# WS2812RGB.net
KiCad netlist of a schematic drawn in Altium Designer
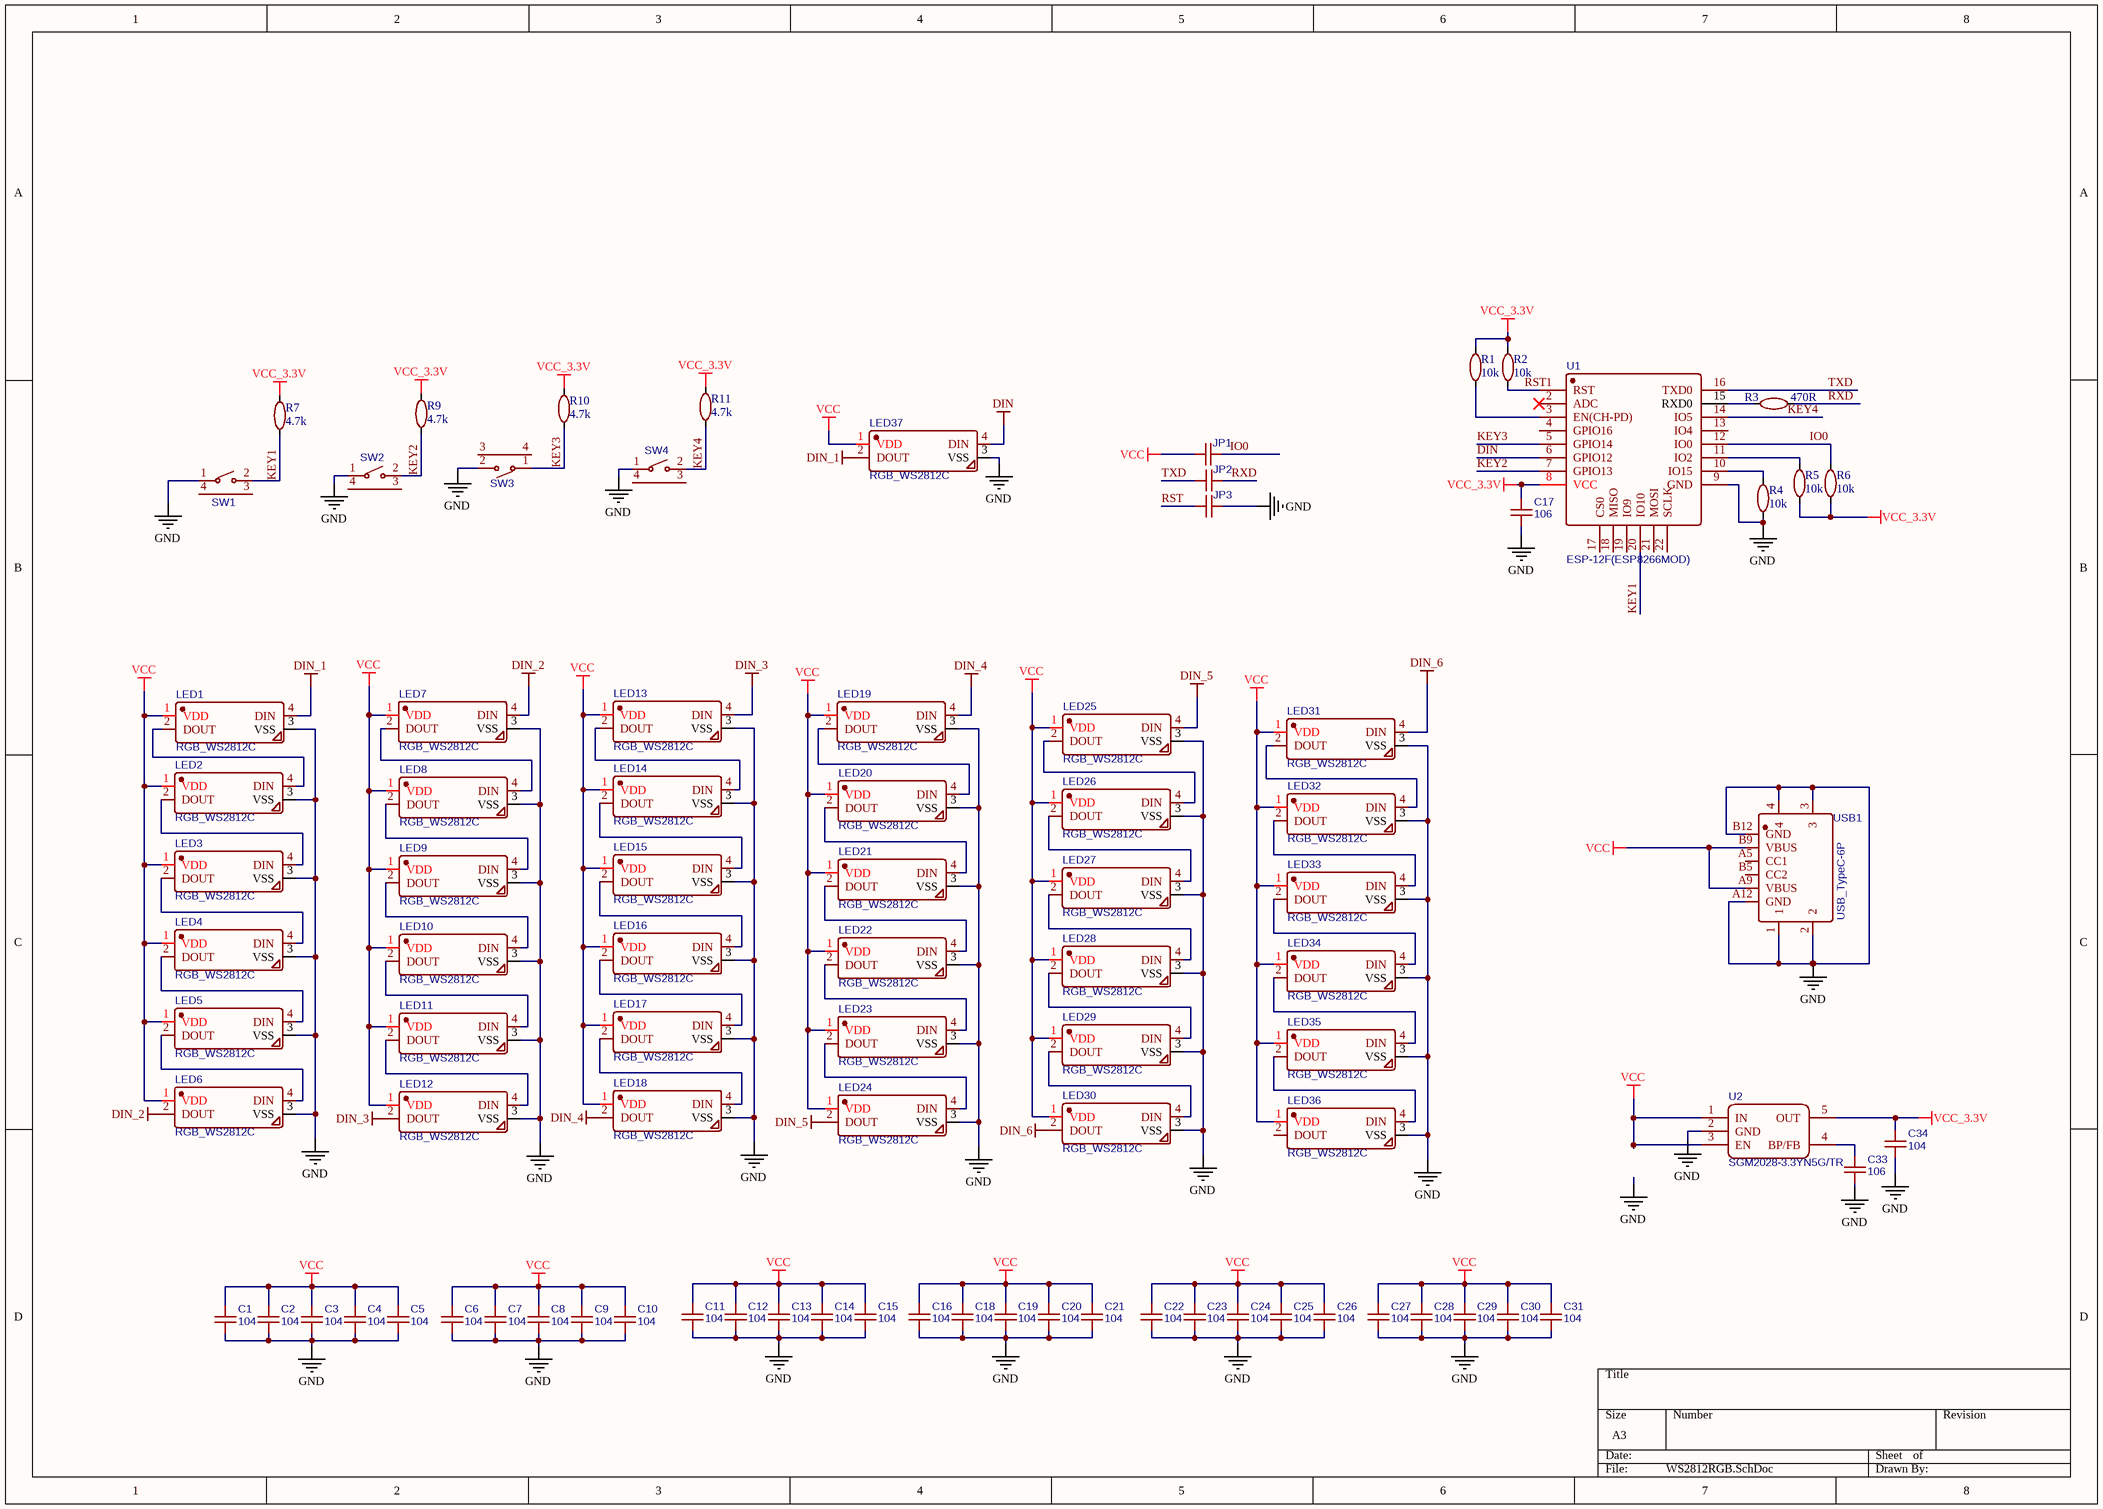
[diagram p0: WS2812RGB.SchDoc]

(export (version "E")
  (design (tool "Eeschema 10.0.6"))
  (components
    (comp (ref "C1")
      (value "104")
      (footprint "CAP_0603")
      (fields
        (field (name "BOM_SUPPLIER PART") "C307348")
        (field (name "BOM_MANUFACTURER PART") "CL10B104KB8WPNC")
        (field (name "CONTRIBUTOR") "LCSC")
      )
      (libsource (lib "LTC_Library1") (part "CAP_0603"))
    )
    (comp (ref "C2")
      (value "104")
      (footprint "CAP_0603")
      (fields
        (field (name "BOM_SUPPLIER PART") "C307348")
        (field (name "BOM_MANUFACTURER PART") "CL10B104KB8WPNC")
        (field (name "CONTRIBUTOR") "LCSC")
      )
      (libsource (lib "LTC_Library1") (part "CAP_0603"))
    )
    (comp (ref "C3")
      (value "104")
      (footprint "CAP_0603")
      (fields
        (field (name "BOM_SUPPLIER PART") "C307348")
        (field (name "BOM_MANUFACTURER PART") "CL10B104KB8WPNC")
        (field (name "CONTRIBUTOR") "LCSC")
      )
      (libsource (lib "LTC_Library1") (part "CAP_0603"))
    )
    (comp (ref "C4")
      (value "104")
      (footprint "CAP_0603")
      (fields
        (field (name "BOM_SUPPLIER PART") "C307348")
        (field (name "BOM_MANUFACTURER PART") "CL10B104KB8WPNC")
        (field (name "CONTRIBUTOR") "LCSC")
      )
      (libsource (lib "LTC_Library1") (part "CAP_0603"))
    )
    (comp (ref "C5")
      (value "104")
      (footprint "CAP_0603")
      (fields
        (field (name "BOM_SUPPLIER PART") "C307348")
        (field (name "BOM_MANUFACTURER PART") "CL10B104KB8WPNC")
        (field (name "CONTRIBUTOR") "LCSC")
      )
      (libsource (lib "LTC_Library1") (part "CAP_0603"))
    )
    (comp (ref "C6")
      (value "104")
      (footprint "CAP_0603")
      (fields
        (field (name "BOM_SUPPLIER PART") "C307348")
        (field (name "BOM_MANUFACTURER PART") "CL10B104KB8WPNC")
        (field (name "CONTRIBUTOR") "LCSC")
      )
      (libsource (lib "LTC_Library1") (part "CAP_0603"))
    )
    (comp (ref "C7")
      (value "104")
      (footprint "CAP_0603")
      (fields
        (field (name "BOM_SUPPLIER PART") "C307348")
        (field (name "BOM_MANUFACTURER PART") "CL10B104KB8WPNC")
        (field (name "CONTRIBUTOR") "LCSC")
      )
      (libsource (lib "LTC_Library1") (part "CAP_0603"))
    )
    (comp (ref "C8")
      (value "104")
      (footprint "CAP_0603")
      (fields
        (field (name "BOM_SUPPLIER PART") "C307348")
        (field (name "BOM_MANUFACTURER PART") "CL10B104KB8WPNC")
        (field (name "CONTRIBUTOR") "LCSC")
      )
      (libsource (lib "LTC_Library1") (part "CAP_0603"))
    )
    (comp (ref "C9")
      (value "104")
      (footprint "CAP_0603")
      (fields
        (field (name "BOM_SUPPLIER PART") "C307348")
        (field (name "BOM_MANUFACTURER PART") "CL10B104KB8WPNC")
        (field (name "CONTRIBUTOR") "LCSC")
      )
      (libsource (lib "LTC_Library1") (part "CAP_0603"))
    )
    (comp (ref "C10")
      (value "104")
      (footprint "CAP_0603")
      (fields
        (field (name "BOM_SUPPLIER PART") "C307348")
        (field (name "BOM_MANUFACTURER PART") "CL10B104KB8WPNC")
        (field (name "CONTRIBUTOR") "LCSC")
      )
      (libsource (lib "LTC_Library1") (part "CAP_0603"))
    )
    (comp (ref "C11")
      (value "104")
      (footprint "CAP_0603")
      (fields
        (field (name "BOM_SUPPLIER PART") "C307348")
        (field (name "BOM_MANUFACTURER PART") "CL10B104KB8WPNC")
        (field (name "CONTRIBUTOR") "LCSC")
      )
      (libsource (lib "LTC_Library1") (part "CAP_0603"))
    )
    (comp (ref "C12")
      (value "104")
      (footprint "CAP_0603")
      (fields
        (field (name "BOM_SUPPLIER PART") "C307348")
        (field (name "BOM_MANUFACTURER PART") "CL10B104KB8WPNC")
        (field (name "CONTRIBUTOR") "LCSC")
      )
      (libsource (lib "LTC_Library1") (part "CAP_0603"))
    )
    (comp (ref "C13")
      (value "104")
      (footprint "CAP_0603")
      (fields
        (field (name "BOM_SUPPLIER PART") "C307348")
        (field (name "BOM_MANUFACTURER PART") "CL10B104KB8WPNC")
        (field (name "CONTRIBUTOR") "LCSC")
      )
      (libsource (lib "LTC_Library1") (part "CAP_0603"))
    )
    (comp (ref "C14")
      (value "104")
      (footprint "CAP_0603")
      (fields
        (field (name "BOM_SUPPLIER PART") "C307348")
        (field (name "BOM_MANUFACTURER PART") "CL10B104KB8WPNC")
        (field (name "CONTRIBUTOR") "LCSC")
      )
      (libsource (lib "LTC_Library1") (part "CAP_0603"))
    )
    (comp (ref "C15")
      (value "104")
      (footprint "CAP_0603")
      (fields
        (field (name "BOM_SUPPLIER PART") "C307348")
        (field (name "BOM_MANUFACTURER PART") "CL10B104KB8WPNC")
        (field (name "CONTRIBUTOR") "LCSC")
      )
      (libsource (lib "LTC_Library1") (part "CAP_0603"))
    )
    (comp (ref "C16")
      (value "104")
      (footprint "CAP_0603")
      (fields
        (field (name "BOM_SUPPLIER PART") "C307348")
        (field (name "BOM_MANUFACTURER PART") "CL10B104KB8WPNC")
        (field (name "CONTRIBUTOR") "LCSC")
      )
      (libsource (lib "LTC_Library1") (part "CAP_0603"))
    )
    (comp (ref "C17")
      (value "106")
      (footprint "CAP_0603")
      (fields
        (field (name "BOM_SUPPLIER PART") "C307348")
        (field (name "BOM_MANUFACTURER PART") "CL10B104KB8WPNC")
        (field (name "CONTRIBUTOR") "LCSC")
      )
      (libsource (lib "LTC_Library1") (part "CAP_0603"))
    )
    (comp (ref "C18")
      (value "104")
      (footprint "CAP_0603")
      (fields
        (field (name "BOM_SUPPLIER PART") "C307348")
        (field (name "BOM_MANUFACTURER PART") "CL10B104KB8WPNC")
        (field (name "CONTRIBUTOR") "LCSC")
      )
      (libsource (lib "LTC_Library1") (part "CAP_0603"))
    )
    (comp (ref "C19")
      (value "104")
      (footprint "CAP_0603")
      (fields
        (field (name "BOM_SUPPLIER PART") "C307348")
        (field (name "BOM_MANUFACTURER PART") "CL10B104KB8WPNC")
        (field (name "CONTRIBUTOR") "LCSC")
      )
      (libsource (lib "LTC_Library1") (part "CAP_0603"))
    )
    (comp (ref "C20")
      (value "104")
      (footprint "CAP_0603")
      (fields
        (field (name "BOM_SUPPLIER PART") "C307348")
        (field (name "BOM_MANUFACTURER PART") "CL10B104KB8WPNC")
        (field (name "CONTRIBUTOR") "LCSC")
      )
      (libsource (lib "LTC_Library1") (part "CAP_0603"))
    )
    (comp (ref "C21")
      (value "104")
      (footprint "CAP_0603")
      (fields
        (field (name "BOM_SUPPLIER PART") "C307348")
        (field (name "BOM_MANUFACTURER PART") "CL10B104KB8WPNC")
        (field (name "CONTRIBUTOR") "LCSC")
      )
      (libsource (lib "LTC_Library1") (part "CAP_0603"))
    )
    (comp (ref "C22")
      (value "104")
      (footprint "CAP_0603")
      (fields
        (field (name "BOM_SUPPLIER PART") "C307348")
        (field (name "BOM_MANUFACTURER PART") "CL10B104KB8WPNC")
        (field (name "CONTRIBUTOR") "LCSC")
      )
      (libsource (lib "LTC_Library1") (part "CAP_0603"))
    )
    (comp (ref "C23")
      (value "104")
      (footprint "CAP_0603")
      (fields
        (field (name "BOM_SUPPLIER PART") "C307348")
        (field (name "BOM_MANUFACTURER PART") "CL10B104KB8WPNC")
        (field (name "CONTRIBUTOR") "LCSC")
      )
      (libsource (lib "LTC_Library1") (part "CAP_0603"))
    )
    (comp (ref "C24")
      (value "104")
      (footprint "CAP_0603")
      (fields
        (field (name "BOM_SUPPLIER PART") "C307348")
        (field (name "BOM_MANUFACTURER PART") "CL10B104KB8WPNC")
        (field (name "CONTRIBUTOR") "LCSC")
      )
      (libsource (lib "LTC_Library1") (part "CAP_0603"))
    )
    (comp (ref "C25")
      (value "104")
      (footprint "CAP_0603")
      (fields
        (field (name "BOM_SUPPLIER PART") "C307348")
        (field (name "BOM_MANUFACTURER PART") "CL10B104KB8WPNC")
        (field (name "CONTRIBUTOR") "LCSC")
      )
      (libsource (lib "LTC_Library1") (part "CAP_0603"))
    )
    (comp (ref "C26")
      (value "104")
      (footprint "CAP_0603")
      (fields
        (field (name "BOM_SUPPLIER PART") "C307348")
        (field (name "BOM_MANUFACTURER PART") "CL10B104KB8WPNC")
        (field (name "CONTRIBUTOR") "LCSC")
      )
      (libsource (lib "LTC_Library1") (part "CAP_0603"))
    )
    (comp (ref "C27")
      (value "104")
      (footprint "CAP_0603")
      (fields
        (field (name "BOM_SUPPLIER PART") "C307348")
        (field (name "BOM_MANUFACTURER PART") "CL10B104KB8WPNC")
        (field (name "CONTRIBUTOR") "LCSC")
      )
      (libsource (lib "LTC_Library1") (part "CAP_0603"))
    )
    (comp (ref "C28")
      (value "104")
      (footprint "CAP_0603")
      (fields
        (field (name "BOM_SUPPLIER PART") "C307348")
        (field (name "BOM_MANUFACTURER PART") "CL10B104KB8WPNC")
        (field (name "CONTRIBUTOR") "LCSC")
      )
      (libsource (lib "LTC_Library1") (part "CAP_0603"))
    )
    (comp (ref "C29")
      (value "104")
      (footprint "CAP_0603")
      (fields
        (field (name "BOM_SUPPLIER PART") "C307348")
        (field (name "BOM_MANUFACTURER PART") "CL10B104KB8WPNC")
        (field (name "CONTRIBUTOR") "LCSC")
      )
      (libsource (lib "LTC_Library1") (part "CAP_0603"))
    )
    (comp (ref "C30")
      (value "104")
      (footprint "CAP_0603")
      (fields
        (field (name "BOM_SUPPLIER PART") "C307348")
        (field (name "BOM_MANUFACTURER PART") "CL10B104KB8WPNC")
        (field (name "CONTRIBUTOR") "LCSC")
      )
      (libsource (lib "LTC_Library1") (part "CAP_0603"))
    )
    (comp (ref "C31")
      (value "104")
      (footprint "CAP_0603")
      (fields
        (field (name "BOM_SUPPLIER PART") "C307348")
        (field (name "BOM_MANUFACTURER PART") "CL10B104KB8WPNC")
        (field (name "CONTRIBUTOR") "LCSC")
      )
      (libsource (lib "LTC_Library1") (part "CAP_0603"))
    )
    (comp (ref "C33")
      (value "106")
      (footprint "CAP_0603")
      (fields
        (field (name "BOM_SUPPLIER PART") "C307348")
        (field (name "BOM_MANUFACTURER PART") "CL10B104KB8WPNC")
        (field (name "CONTRIBUTOR") "LCSC")
      )
      (libsource (lib "LTC_Library1") (part "CAP_0603"))
    )
    (comp (ref "C34")
      (value "104")
      (footprint "CAP_0603")
      (fields
        (field (name "BOM_SUPPLIER PART") "C307348")
        (field (name "BOM_MANUFACTURER PART") "CL10B104KB8WPNC")
        (field (name "CONTRIBUTOR") "LCSC")
      )
      (libsource (lib "LTC_Library1") (part "CAP_0603"))
    )
    (comp (ref "JP1")
      (value "104")
      (footprint "CAP_0805")
      (fields
        (field (name "BOM_SUPPLIER PART") "C307348")
        (field (name "BOM_MANUFACTURER PART") "CL10B104KB8WPNC")
        (field (name "CONTRIBUTOR") "LCSC")
      )
      (libsource (lib "LTC_Library1") (part "CAP_0805"))
    )
    (comp (ref "JP2")
      (value "104")
      (footprint "CAP_0805")
      (fields
        (field (name "BOM_SUPPLIER PART") "C307348")
        (field (name "BOM_MANUFACTURER PART") "CL10B104KB8WPNC")
        (field (name "CONTRIBUTOR") "LCSC")
      )
      (libsource (lib "LTC_Library1") (part "CAP_0805"))
    )
    (comp (ref "JP3")
      (value "104")
      (footprint "CAP_0805")
      (fields
        (field (name "BOM_SUPPLIER PART") "C307348")
        (field (name "BOM_MANUFACTURER PART") "CL10B104KB8WPNC")
        (field (name "CONTRIBUTOR") "LCSC")
      )
      (libsource (lib "LTC_Library1") (part "CAP_0805"))
    )
    (comp (ref "LED1")
      (value "RGB_WS2812C")
      (footprint "LED_5050-SMD_4P-WS2812")
      (fields
        (field (name "BOM_MANUFACTURER PART") "WS2812C")
        (field (name "BOM_SUPPLIER PART") "C114587")
        (field (name "CONTRIBUTOR") "LCSC")
      )
      (libsource (lib "LTC_Library1") (part "RGB_WS2812C"))
    )
    (comp (ref "LED2")
      (value "RGB_WS2812C")
      (footprint "LED_5050-SMD_4P-WS2812")
      (fields
        (field (name "BOM_MANUFACTURER PART") "WS2812C")
        (field (name "BOM_SUPPLIER PART") "C114587")
        (field (name "CONTRIBUTOR") "LCSC")
      )
      (libsource (lib "LTC_Library1") (part "RGB_WS2812C"))
    )
    (comp (ref "LED3")
      (value "RGB_WS2812C")
      (footprint "LED_5050-SMD_4P-WS2812")
      (fields
        (field (name "BOM_MANUFACTURER PART") "WS2812C")
        (field (name "BOM_SUPPLIER PART") "C114587")
        (field (name "CONTRIBUTOR") "LCSC")
      )
      (libsource (lib "LTC_Library1") (part "RGB_WS2812C"))
    )
    (comp (ref "LED4")
      (value "RGB_WS2812C")
      (footprint "LED_5050-SMD_4P-WS2812")
      (fields
        (field (name "BOM_MANUFACTURER PART") "WS2812C")
        (field (name "BOM_SUPPLIER PART") "C114587")
        (field (name "CONTRIBUTOR") "LCSC")
      )
      (libsource (lib "LTC_Library1") (part "RGB_WS2812C"))
    )
    (comp (ref "LED5")
      (value "RGB_WS2812C")
      (footprint "LED_5050-SMD_4P-WS2812")
      (fields
        (field (name "BOM_MANUFACTURER PART") "WS2812C")
        (field (name "BOM_SUPPLIER PART") "C114587")
        (field (name "CONTRIBUTOR") "LCSC")
      )
      (libsource (lib "LTC_Library1") (part "RGB_WS2812C"))
    )
    (comp (ref "LED6")
      (value "RGB_WS2812C")
      (footprint "LED_5050-SMD_4P-WS2812")
      (fields
        (field (name "BOM_MANUFACTURER PART") "WS2812C")
        (field (name "BOM_SUPPLIER PART") "C114587")
        (field (name "CONTRIBUTOR") "LCSC")
      )
      (libsource (lib "LTC_Library1") (part "RGB_WS2812C"))
    )
    (comp (ref "LED7")
      (value "RGB_WS2812C")
      (footprint "LED_5050-SMD_4P-WS2812")
      (fields
        (field (name "BOM_MANUFACTURER PART") "WS2812C")
        (field (name "BOM_SUPPLIER PART") "C114587")
        (field (name "CONTRIBUTOR") "LCSC")
      )
      (libsource (lib "LTC_Library1") (part "RGB_WS2812C"))
    )
    (comp (ref "LED8")
      (value "RGB_WS2812C")
      (footprint "LED_5050-SMD_4P-WS2812")
      (fields
        (field (name "BOM_MANUFACTURER PART") "WS2812C")
        (field (name "BOM_SUPPLIER PART") "C114587")
        (field (name "CONTRIBUTOR") "LCSC")
      )
      (libsource (lib "LTC_Library1") (part "RGB_WS2812C"))
    )
    (comp (ref "LED9")
      (value "RGB_WS2812C")
      (footprint "LED_5050-SMD_4P-WS2812")
      (fields
        (field (name "BOM_MANUFACTURER PART") "WS2812C")
        (field (name "BOM_SUPPLIER PART") "C114587")
        (field (name "CONTRIBUTOR") "LCSC")
      )
      (libsource (lib "LTC_Library1") (part "RGB_WS2812C"))
    )
    (comp (ref "LED10")
      (value "RGB_WS2812C")
      (footprint "LED_5050-SMD_4P-WS2812")
      (fields
        (field (name "BOM_MANUFACTURER PART") "WS2812C")
        (field (name "BOM_SUPPLIER PART") "C114587")
        (field (name "CONTRIBUTOR") "LCSC")
      )
      (libsource (lib "LTC_Library1") (part "RGB_WS2812C"))
    )
    (comp (ref "LED11")
      (value "RGB_WS2812C")
      (footprint "LED_5050-SMD_4P-WS2812")
      (fields
        (field (name "BOM_MANUFACTURER PART") "WS2812C")
        (field (name "BOM_SUPPLIER PART") "C114587")
        (field (name "CONTRIBUTOR") "LCSC")
      )
      (libsource (lib "LTC_Library1") (part "RGB_WS2812C"))
    )
    (comp (ref "LED12")
      (value "RGB_WS2812C")
      (footprint "LED_5050-SMD_4P-WS2812")
      (fields
        (field (name "BOM_MANUFACTURER PART") "WS2812C")
        (field (name "BOM_SUPPLIER PART") "C114587")
        (field (name "CONTRIBUTOR") "LCSC")
      )
      (libsource (lib "LTC_Library1") (part "RGB_WS2812C"))
    )
    (comp (ref "LED13")
      (value "RGB_WS2812C")
      (footprint "LED_5050-SMD_4P-WS2812")
      (fields
        (field (name "BOM_MANUFACTURER PART") "WS2812C")
        (field (name "BOM_SUPPLIER PART") "C114587")
        (field (name "CONTRIBUTOR") "LCSC")
      )
      (libsource (lib "LTC_Library1") (part "RGB_WS2812C"))
    )
    (comp (ref "LED14")
      (value "RGB_WS2812C")
      (footprint "LED_5050-SMD_4P-WS2812")
      (fields
        (field (name "BOM_MANUFACTURER PART") "WS2812C")
        (field (name "BOM_SUPPLIER PART") "C114587")
        (field (name "CONTRIBUTOR") "LCSC")
      )
      (libsource (lib "LTC_Library1") (part "RGB_WS2812C"))
    )
    (comp (ref "LED15")
      (value "RGB_WS2812C")
      (footprint "LED_5050-SMD_4P-WS2812")
      (fields
        (field (name "BOM_MANUFACTURER PART") "WS2812C")
        (field (name "BOM_SUPPLIER PART") "C114587")
        (field (name "CONTRIBUTOR") "LCSC")
      )
      (libsource (lib "LTC_Library1") (part "RGB_WS2812C"))
    )
    (comp (ref "LED16")
      (value "RGB_WS2812C")
      (footprint "LED_5050-SMD_4P-WS2812")
      (fields
        (field (name "BOM_MANUFACTURER PART") "WS2812C")
        (field (name "BOM_SUPPLIER PART") "C114587")
        (field (name "CONTRIBUTOR") "LCSC")
      )
      (libsource (lib "LTC_Library1") (part "RGB_WS2812C"))
    )
    (comp (ref "LED17")
      (value "RGB_WS2812C")
      (footprint "LED_5050-SMD_4P-WS2812")
      (fields
        (field (name "BOM_MANUFACTURER PART") "WS2812C")
        (field (name "BOM_SUPPLIER PART") "C114587")
        (field (name "CONTRIBUTOR") "LCSC")
      )
      (libsource (lib "LTC_Library1") (part "RGB_WS2812C"))
    )
    (comp (ref "LED18")
      (value "RGB_WS2812C")
      (footprint "LED_5050-SMD_4P-WS2812")
      (fields
        (field (name "BOM_MANUFACTURER PART") "WS2812C")
        (field (name "BOM_SUPPLIER PART") "C114587")
        (field (name "CONTRIBUTOR") "LCSC")
      )
      (libsource (lib "LTC_Library1") (part "RGB_WS2812C"))
    )
    (comp (ref "LED19")
      (value "RGB_WS2812C")
      (footprint "LED_5050-SMD_4P-WS2812")
      (fields
        (field (name "BOM_MANUFACTURER PART") "WS2812C")
        (field (name "BOM_SUPPLIER PART") "C114587")
        (field (name "CONTRIBUTOR") "LCSC")
      )
      (libsource (lib "LTC_Library1") (part "RGB_WS2812C"))
    )
    (comp (ref "LED20")
      (value "RGB_WS2812C")
      (footprint "LED_5050-SMD_4P-WS2812")
      (fields
        (field (name "BOM_MANUFACTURER PART") "WS2812C")
        (field (name "BOM_SUPPLIER PART") "C114587")
        (field (name "CONTRIBUTOR") "LCSC")
      )
      (libsource (lib "LTC_Library1") (part "RGB_WS2812C"))
    )
    (comp (ref "LED21")
      (value "RGB_WS2812C")
      (footprint "LED_5050-SMD_4P-WS2812")
      (fields
        (field (name "BOM_MANUFACTURER PART") "WS2812C")
        (field (name "BOM_SUPPLIER PART") "C114587")
        (field (name "CONTRIBUTOR") "LCSC")
      )
      (libsource (lib "LTC_Library1") (part "RGB_WS2812C"))
    )
    (comp (ref "LED22")
      (value "RGB_WS2812C")
      (footprint "LED_5050-SMD_4P-WS2812")
      (fields
        (field (name "BOM_MANUFACTURER PART") "WS2812C")
        (field (name "BOM_SUPPLIER PART") "C114587")
        (field (name "CONTRIBUTOR") "LCSC")
      )
      (libsource (lib "LTC_Library1") (part "RGB_WS2812C"))
    )
    (comp (ref "LED23")
      (value "RGB_WS2812C")
      (footprint "LED_5050-SMD_4P-WS2812")
      (fields
        (field (name "BOM_MANUFACTURER PART") "WS2812C")
        (field (name "BOM_SUPPLIER PART") "C114587")
        (field (name "CONTRIBUTOR") "LCSC")
      )
      (libsource (lib "LTC_Library1") (part "RGB_WS2812C"))
    )
    (comp (ref "LED24")
      (value "RGB_WS2812C")
      (footprint "LED_5050-SMD_4P-WS2812")
      (fields
        (field (name "BOM_MANUFACTURER PART") "WS2812C")
        (field (name "BOM_SUPPLIER PART") "C114587")
        (field (name "CONTRIBUTOR") "LCSC")
      )
      (libsource (lib "LTC_Library1") (part "RGB_WS2812C"))
    )
    (comp (ref "LED25")
      (value "RGB_WS2812C")
      (footprint "LED_5050-SMD_4P-WS2812")
      (fields
        (field (name "BOM_MANUFACTURER PART") "WS2812C")
        (field (name "BOM_SUPPLIER PART") "C114587")
        (field (name "CONTRIBUTOR") "LCSC")
      )
      (libsource (lib "LTC_Library1") (part "RGB_WS2812C"))
    )
    (comp (ref "LED26")
      (value "RGB_WS2812C")
      (footprint "LED_5050-SMD_4P-WS2812")
      (fields
        (field (name "BOM_MANUFACTURER PART") "WS2812C")
        (field (name "BOM_SUPPLIER PART") "C114587")
        (field (name "CONTRIBUTOR") "LCSC")
      )
      (libsource (lib "LTC_Library1") (part "RGB_WS2812C"))
    )
    (comp (ref "LED27")
      (value "RGB_WS2812C")
      (footprint "LED_5050-SMD_4P-WS2812")
      (fields
        (field (name "BOM_MANUFACTURER PART") "WS2812C")
        (field (name "BOM_SUPPLIER PART") "C114587")
        (field (name "CONTRIBUTOR") "LCSC")
      )
      (libsource (lib "LTC_Library1") (part "RGB_WS2812C"))
    )
    (comp (ref "LED28")
      (value "RGB_WS2812C")
      (footprint "LED_5050-SMD_4P-WS2812")
      (fields
        (field (name "BOM_MANUFACTURER PART") "WS2812C")
        (field (name "BOM_SUPPLIER PART") "C114587")
        (field (name "CONTRIBUTOR") "LCSC")
      )
      (libsource (lib "LTC_Library1") (part "RGB_WS2812C"))
    )
    (comp (ref "LED29")
      (value "RGB_WS2812C")
      (footprint "LED_5050-SMD_4P-WS2812")
      (fields
        (field (name "BOM_MANUFACTURER PART") "WS2812C")
        (field (name "BOM_SUPPLIER PART") "C114587")
        (field (name "CONTRIBUTOR") "LCSC")
      )
      (libsource (lib "LTC_Library1") (part "RGB_WS2812C"))
    )
    (comp (ref "LED30")
      (value "RGB_WS2812C")
      (footprint "LED_5050-SMD_4P-WS2812")
      (fields
        (field (name "BOM_MANUFACTURER PART") "WS2812C")
        (field (name "BOM_SUPPLIER PART") "C114587")
        (field (name "CONTRIBUTOR") "LCSC")
      )
      (libsource (lib "LTC_Library1") (part "RGB_WS2812C"))
    )
    (comp (ref "LED31")
      (value "RGB_WS2812C")
      (footprint "LED_5050-SMD_4P-WS2812")
      (fields
        (field (name "BOM_MANUFACTURER PART") "WS2812C")
        (field (name "BOM_SUPPLIER PART") "C114587")
        (field (name "CONTRIBUTOR") "LCSC")
      )
      (libsource (lib "LTC_Library1") (part "RGB_WS2812C"))
    )
    (comp (ref "LED32")
      (value "RGB_WS2812C")
      (footprint "LED_5050-SMD_4P-WS2812")
      (fields
        (field (name "BOM_MANUFACTURER PART") "WS2812C")
        (field (name "BOM_SUPPLIER PART") "C114587")
        (field (name "CONTRIBUTOR") "LCSC")
      )
      (libsource (lib "LTC_Library1") (part "RGB_WS2812C"))
    )
    (comp (ref "LED33")
      (value "RGB_WS2812C")
      (footprint "LED_5050-SMD_4P-WS2812")
      (fields
        (field (name "BOM_MANUFACTURER PART") "WS2812C")
        (field (name "BOM_SUPPLIER PART") "C114587")
        (field (name "CONTRIBUTOR") "LCSC")
      )
      (libsource (lib "LTC_Library1") (part "RGB_WS2812C"))
    )
    (comp (ref "LED34")
      (value "RGB_WS2812C")
      (footprint "LED_5050-SMD_4P-WS2812")
      (fields
        (field (name "BOM_MANUFACTURER PART") "WS2812C")
        (field (name "BOM_SUPPLIER PART") "C114587")
        (field (name "CONTRIBUTOR") "LCSC")
      )
      (libsource (lib "LTC_Library1") (part "RGB_WS2812C"))
    )
    (comp (ref "LED35")
      (value "RGB_WS2812C")
      (footprint "LED_5050-SMD_4P-WS2812")
      (fields
        (field (name "BOM_MANUFACTURER PART") "WS2812C")
        (field (name "BOM_SUPPLIER PART") "C114587")
        (field (name "CONTRIBUTOR") "LCSC")
      )
      (libsource (lib "LTC_Library1") (part "RGB_WS2812C"))
    )
    (comp (ref "LED36")
      (value "RGB_WS2812C")
      (footprint "LED_5050-SMD_4P-WS2812")
      (fields
        (field (name "BOM_MANUFACTURER PART") "WS2812C")
        (field (name "BOM_SUPPLIER PART") "C114587")
        (field (name "CONTRIBUTOR") "LCSC")
      )
      (libsource (lib "LTC_Library1") (part "RGB_WS2812C"))
    )
    (comp (ref "LED37")
      (value "RGB_WS2812C")
      (footprint "LED_5050-SMD_4P-WS2812")
      (fields
        (field (name "BOM_MANUFACTURER PART") "WS2812C")
        (field (name "BOM_SUPPLIER PART") "C114587")
        (field (name "CONTRIBUTOR") "LCSC")
      )
      (libsource (lib "LTC_Library1") (part "RGB_WS2812C"))
    )
    (comp (ref "R1") (value "10k") (footprint "RES_0402") (libsource (lib "LTC_Library1") (part "RES_0402")))
    (comp (ref "R2") (value "10k") (footprint "RES_0402") (libsource (lib "LTC_Library1") (part "RES_0402")))
    (comp (ref "R3") (value "470R") (footprint "RES_0402") (libsource (lib "LTC_Library1") (part "RES_0402")))
    (comp (ref "R4") (value "10k") (footprint "RES_0402") (libsource (lib "LTC_Library1") (part "RES_0402")))
    (comp (ref "R5") (value "10k") (footprint "RES_0402") (libsource (lib "LTC_Library1") (part "RES_0402")))
    (comp (ref "R6") (value "10k") (footprint "RES_0402") (libsource (lib "LTC_Library1") (part "RES_0402")))
    (comp (ref "R7") (value "4.7k") (footprint "RES_0402") (libsource (lib "LTC_Library1") (part "RES_0402")))
    (comp (ref "R9") (value "4.7k") (footprint "RES_0402") (libsource (lib "LTC_Library1") (part "RES_0402")))
    (comp (ref "R10")
      (value "4.7k")
      (footprint "RES_0402")
      (libsource (lib "LTC_Library1") (part "RES_0402"))
    )
    (comp (ref "R11")
      (value "4.7k")
      (footprint "RES_0402")
      (libsource (lib "LTC_Library1") (part "RES_0402"))
    )
    (comp (ref "SW1")
      (value "TS-1086E-16")
      (footprint "SW-SMD_TS-1086E-16")
      (fields (field (name "BOM_SUPPLIER PART") "C455276") (field (name "CONTRIBUTOR") "LCSC"))
      (libsource (lib "LTC_Library1") (part "TS-1086E-16"))
    )
    (comp (ref "SW2")
      (value "TS-1086E-16")
      (footprint "SW-SMD_TS-1086E-16")
      (fields (field (name "BOM_SUPPLIER PART") "C455276") (field (name "CONTRIBUTOR") "LCSC"))
      (libsource (lib "LTC_Library1") (part "TS-1086E-16"))
    )
    (comp (ref "SW3")
      (value "TS-1086E-16")
      (footprint "SW-SMD_TS-1086E-16")
      (fields (field (name "BOM_SUPPLIER PART") "C455276") (field (name "CONTRIBUTOR") "LCSC"))
      (libsource (lib "LTC_Library1") (part "TS-1086E-16"))
    )
    (comp (ref "SW4")
      (value "TS-1086E-16")
      (footprint "SW-SMD_TS-1086E-16")
      (fields (field (name "BOM_SUPPLIER PART") "C455276") (field (name "CONTRIBUTOR") "LCSC"))
      (libsource (lib "LTC_Library1") (part "TS-1086E-16"))
    )
    (comp (ref "U1")
      (value "ESP-12F(ESP8266MOD)")
      (footprint "WIFIM-SMD_ESP-12F-ESP8266MOD")
      (fields (field (name "BOM_SUPPLIER PART") "C82891"))
      (libsource (lib "LTC_Library1") (part "ESP-12F(ESP8266MOD)"))
    )
    (comp (ref "U2")
      (value "SGM2028-3.3YN5G/TR")
      (footprint "SOT23_5")
      (fields (field (name "BOM_SUPPLIER PART") "C81088"))
      (libsource (lib "LTC_Library1") (part "SGM2028-3.3YN5G/TR"))
    )
    (comp (ref "USB1")
      (value "USB_TypeC-6P")
      (footprint "USB-TYPE-C-SMD")
      (fields
        (field (name "BOM_SUPPLIER PART") "C399925")
        (field (name "BOM_MANUFACTURER PART") "918-418K2023S40006")
        (field (name "CONTRIBUTOR") "LCSC")
      )
      (libsource (lib "LTC_Library1") (part "USB_TypeC-6P"))
    )
  )
  (nets
    (net (code "1") (name "/IO0") (class "Default")
      (node (ref "JP1") (pin "2") (pinfunction "2_2") (pintype "passive"))
      (node (ref "R6") (pin "1") (pinfunction "1_1") (pintype "passive"))
      (node (ref "U1") (pin "12") (pinfunction "IO0_12") (pintype "passive"))
    )
    (net (code "2") (name "/KEY1") (class "Default")
      (node (ref "R7") (pin "2") (pinfunction "2_2") (pintype "passive"))
      (node (ref "SW1") (pin "2") (pinfunction "2_2") (pintype "passive"))
      (node (ref "U1") (pin "20") (pinfunction "IO10_20") (pintype "passive"))
    )
    (net (code "3") (name "/KEY2") (class "Default")
      (node (ref "R9") (pin "2") (pinfunction "2_2") (pintype "passive"))
      (node (ref "SW2") (pin "2") (pinfunction "2_2") (pintype "passive"))
      (node (ref "U1") (pin "7") (pinfunction "GPIO13_7") (pintype "passive"))
    )
    (net (code "4") (name "/KEY3") (class "Default")
      (node (ref "R10") (pin "2") (pinfunction "2_2") (pintype "passive"))
      (node (ref "SW3") (pin "1") (pinfunction "1_1") (pintype "passive"))
      (node (ref "U1") (pin "5") (pinfunction "GPIO14_5") (pintype "passive"))
    )
    (net (code "5") (name "/KEY4") (class "Default")
      (node (ref "R11") (pin "2") (pinfunction "2_2") (pintype "passive"))
      (node (ref "SW4") (pin "2") (pinfunction "2_2") (pintype "passive"))
      (node (ref "U1") (pin "14") (pinfunction "IO5_14") (pintype "passive"))
    )
    (net (code "6") (name "/RST") (class "Default")
      (node (ref "JP3") (pin "1") (pinfunction "1_1") (pintype "passive"))
      (node (ref "R2") (pin "2") (pinfunction "2_2") (pintype "passive"))
      (node (ref "U1") (pin "1") (pinfunction "RST_1") (pintype "passive"))
    )
    (net (code "7") (name "/RXD") (class "Default")
      (node (ref "JP2") (pin "2") (pinfunction "2_2") (pintype "passive"))
      (node (ref "R3") (pin "2") (pinfunction "2_2") (pintype "passive"))
    )
    (net (code "8") (name "/TXD") (class "Default")
      (node (ref "JP2") (pin "1") (pinfunction "1_1") (pintype "passive"))
      (node (ref "U1") (pin "16") (pinfunction "TXD0_16") (pintype "passive"))
    )
    (net (code "9") (name "DIN") (class "Default")
      (node (ref "LED37") (pin "4") (pinfunction "DIN_4") (pintype "passive"))
      (node (ref "U1") (pin "6") (pinfunction "GPIO12_6") (pintype "passive"))
    )
    (net (code "10") (name "DIN_1") (class "Default")
      (node (ref "LED1") (pin "4") (pinfunction "DIN_4") (pintype "passive"))
      (node (ref "LED37") (pin "2") (pinfunction "DOUT_2") (pintype "passive"))
    )
    (net (code "11") (name "DIN_2") (class "Default")
      (node (ref "LED6") (pin "2") (pinfunction "DOUT_2") (pintype "passive"))
      (node (ref "LED7") (pin "4") (pinfunction "DIN_4") (pintype "passive"))
    )
    (net (code "12") (name "DIN_3") (class "Default")
      (node (ref "LED12") (pin "2") (pinfunction "DOUT_2") (pintype "passive"))
      (node (ref "LED13") (pin "4") (pinfunction "DIN_4") (pintype "passive"))
    )
    (net (code "13") (name "DIN_4") (class "Default")
      (node (ref "LED18") (pin "2") (pinfunction "DOUT_2") (pintype "passive"))
      (node (ref "LED19") (pin "4") (pinfunction "DIN_4") (pintype "passive"))
    )
    (net (code "14") (name "DIN_5") (class "Default")
      (node (ref "LED24") (pin "2") (pinfunction "DOUT_2") (pintype "passive"))
      (node (ref "LED25") (pin "4") (pinfunction "DIN_4") (pintype "passive"))
    )
    (net (code "15") (name "DIN_6") (class "Default")
      (node (ref "LED30") (pin "2") (pinfunction "DOUT_2") (pintype "passive"))
      (node (ref "LED31") (pin "4") (pinfunction "DIN_4") (pintype "passive"))
    )
    (net (code "16") (name "GND") (class "Default")
      (node (ref "C1") (pin "2") (pinfunction "2_2") (pintype "passive"))
      (node (ref "C10") (pin "2") (pinfunction "2_2") (pintype "passive"))
      (node (ref "C11") (pin "2") (pinfunction "2_2") (pintype "passive"))
      (node (ref "C12") (pin "2") (pinfunction "2_2") (pintype "passive"))
      (node (ref "C13") (pin "2") (pinfunction "2_2") (pintype "passive"))
      (node (ref "C14") (pin "2") (pinfunction "2_2") (pintype "passive"))
      (node (ref "C15") (pin "2") (pinfunction "2_2") (pintype "passive"))
      (node (ref "C16") (pin "2") (pinfunction "2_2") (pintype "passive"))
      (node (ref "C17") (pin "2") (pinfunction "2_2") (pintype "passive"))
      (node (ref "C18") (pin "2") (pinfunction "2_2") (pintype "passive"))
      (node (ref "C19") (pin "2") (pinfunction "2_2") (pintype "passive"))
      (node (ref "C2") (pin "2") (pinfunction "2_2") (pintype "passive"))
      (node (ref "C20") (pin "2") (pinfunction "2_2") (pintype "passive"))
      (node (ref "C21") (pin "2") (pinfunction "2_2") (pintype "passive"))
      (node (ref "C22") (pin "2") (pinfunction "2_2") (pintype "passive"))
      (node (ref "C23") (pin "2") (pinfunction "2_2") (pintype "passive"))
      (node (ref "C24") (pin "2") (pinfunction "2_2") (pintype "passive"))
      (node (ref "C25") (pin "2") (pinfunction "2_2") (pintype "passive"))
      (node (ref "C26") (pin "2") (pinfunction "2_2") (pintype "passive"))
      (node (ref "C27") (pin "2") (pinfunction "2_2") (pintype "passive"))
      (node (ref "C28") (pin "2") (pinfunction "2_2") (pintype "passive"))
      (node (ref "C29") (pin "2") (pinfunction "2_2") (pintype "passive"))
      (node (ref "C3") (pin "2") (pinfunction "2_2") (pintype "passive"))
      (node (ref "C30") (pin "2") (pinfunction "2_2") (pintype "passive"))
      (node (ref "C31") (pin "2") (pinfunction "2_2") (pintype "passive"))
      (node (ref "C33") (pin "2") (pinfunction "2_2") (pintype "passive"))
      (node (ref "C34") (pin "2") (pinfunction "2_2") (pintype "passive"))
      (node (ref "C4") (pin "2") (pinfunction "2_2") (pintype "passive"))
      (node (ref "C5") (pin "2") (pinfunction "2_2") (pintype "passive"))
      (node (ref "C6") (pin "2") (pinfunction "2_2") (pintype "passive"))
      (node (ref "C7") (pin "2") (pinfunction "2_2") (pintype "passive"))
      (node (ref "C8") (pin "2") (pinfunction "2_2") (pintype "passive"))
      (node (ref "C9") (pin "2") (pinfunction "2_2") (pintype "passive"))
      (node (ref "JP3") (pin "2") (pinfunction "2_2") (pintype "passive"))
      (node (ref "LED1") (pin "3") (pinfunction "VSS_3") (pintype "passive"))
      (node (ref "LED10") (pin "3") (pinfunction "VSS_3") (pintype "passive"))
      (node (ref "LED11") (pin "3") (pinfunction "VSS_3") (pintype "passive"))
      (node (ref "LED12") (pin "3") (pinfunction "VSS_3") (pintype "passive"))
      (node (ref "LED13") (pin "3") (pinfunction "VSS_3") (pintype "passive"))
      (node (ref "LED14") (pin "3") (pinfunction "VSS_3") (pintype "passive"))
      (node (ref "LED15") (pin "3") (pinfunction "VSS_3") (pintype "passive"))
      (node (ref "LED16") (pin "3") (pinfunction "VSS_3") (pintype "passive"))
      (node (ref "LED17") (pin "3") (pinfunction "VSS_3") (pintype "passive"))
      (node (ref "LED18") (pin "3") (pinfunction "VSS_3") (pintype "passive"))
      (node (ref "LED19") (pin "3") (pinfunction "VSS_3") (pintype "passive"))
      (node (ref "LED2") (pin "3") (pinfunction "VSS_3") (pintype "passive"))
      (node (ref "LED20") (pin "3") (pinfunction "VSS_3") (pintype "passive"))
      (node (ref "LED21") (pin "3") (pinfunction "VSS_3") (pintype "passive"))
      (node (ref "LED22") (pin "3") (pinfunction "VSS_3") (pintype "passive"))
      (node (ref "LED23") (pin "3") (pinfunction "VSS_3") (pintype "passive"))
      (node (ref "LED24") (pin "3") (pinfunction "VSS_3") (pintype "passive"))
      (node (ref "LED25") (pin "3") (pinfunction "VSS_3") (pintype "passive"))
      (node (ref "LED26") (pin "3") (pinfunction "VSS_3") (pintype "passive"))
      (node (ref "LED27") (pin "3") (pinfunction "VSS_3") (pintype "passive"))
      (node (ref "LED28") (pin "3") (pinfunction "VSS_3") (pintype "passive"))
      (node (ref "LED29") (pin "3") (pinfunction "VSS_3") (pintype "passive"))
      (node (ref "LED3") (pin "3") (pinfunction "VSS_3") (pintype "passive"))
      (node (ref "LED30") (pin "3") (pinfunction "VSS_3") (pintype "passive"))
      (node (ref "LED31") (pin "3") (pinfunction "VSS_3") (pintype "passive"))
      (node (ref "LED32") (pin "3") (pinfunction "VSS_3") (pintype "passive"))
      (node (ref "LED33") (pin "3") (pinfunction "VSS_3") (pintype "passive"))
      (node (ref "LED34") (pin "3") (pinfunction "VSS_3") (pintype "passive"))
      (node (ref "LED35") (pin "3") (pinfunction "VSS_3") (pintype "passive"))
      (node (ref "LED36") (pin "3") (pinfunction "VSS_3") (pintype "passive"))
      (node (ref "LED37") (pin "3") (pinfunction "VSS_3") (pintype "passive"))
      (node (ref "LED4") (pin "3") (pinfunction "VSS_3") (pintype "passive"))
      (node (ref "LED5") (pin "3") (pinfunction "VSS_3") (pintype "passive"))
      (node (ref "LED6") (pin "3") (pinfunction "VSS_3") (pintype "passive"))
      (node (ref "LED7") (pin "3") (pinfunction "VSS_3") (pintype "passive"))
      (node (ref "LED8") (pin "3") (pinfunction "VSS_3") (pintype "passive"))
      (node (ref "LED9") (pin "3") (pinfunction "VSS_3") (pintype "passive"))
      (node (ref "R4") (pin "2") (pinfunction "2_2") (pintype "passive"))
      (node (ref "SW1") (pin "1") (pinfunction "1_1") (pintype "passive"))
      (node (ref "SW2") (pin "1") (pinfunction "1_1") (pintype "passive"))
      (node (ref "SW3") (pin "2") (pinfunction "2_2") (pintype "passive"))
      (node (ref "SW4") (pin "1") (pinfunction "1_1") (pintype "passive"))
      (node (ref "U1") (pin "9") (pinfunction "GND_9") (pintype "passive"))
      (node (ref "U2") (pin "2") (pinfunction "GND_2") (pintype "passive"))
      (node (ref "USB1") (pin "1") (pinfunction "1_1") (pintype "passive"))
      (node (ref "USB1") (pin "2") (pinfunction "2_2") (pintype "passive"))
      (node (ref "USB1") (pin "3") (pinfunction "3_3") (pintype "passive"))
      (node (ref "USB1") (pin "4") (pinfunction "4_4") (pintype "passive"))
      (node (ref "USB1") (pin "A12") (pinfunction "GND_A12") (pintype "passive"))
      (node (ref "USB1") (pin "B12") (pinfunction "GND_B12") (pintype "passive"))
    )
    (net (code "17") (name "Net-(LED1-DOUT)") (class "Default")
      (node (ref "LED1") (pin "2") (pinfunction "DOUT_2") (pintype "passive"))
      (node (ref "LED2") (pin "4") (pinfunction "DIN_4") (pintype "passive"))
    )
    (net (code "18") (name "Net-(LED2-DOUT)") (class "Default")
      (node (ref "LED2") (pin "2") (pinfunction "DOUT_2") (pintype "passive"))
      (node (ref "LED3") (pin "4") (pinfunction "DIN_4") (pintype "passive"))
    )
    (net (code "19") (name "Net-(LED3-DOUT)") (class "Default")
      (node (ref "LED3") (pin "2") (pinfunction "DOUT_2") (pintype "passive"))
      (node (ref "LED4") (pin "4") (pinfunction "DIN_4") (pintype "passive"))
    )
    (net (code "20") (name "Net-(LED4-DOUT)") (class "Default")
      (node (ref "LED4") (pin "2") (pinfunction "DOUT_2") (pintype "passive"))
      (node (ref "LED5") (pin "4") (pinfunction "DIN_4") (pintype "passive"))
    )
    (net (code "21") (name "Net-(LED5-DOUT)") (class "Default")
      (node (ref "LED5") (pin "2") (pinfunction "DOUT_2") (pintype "passive"))
      (node (ref "LED6") (pin "4") (pinfunction "DIN_4") (pintype "passive"))
    )
    (net (code "22") (name "Net-(LED7-DOUT)") (class "Default")
      (node (ref "LED7") (pin "2") (pinfunction "DOUT_2") (pintype "passive"))
      (node (ref "LED8") (pin "4") (pinfunction "DIN_4") (pintype "passive"))
    )
    (net (code "23") (name "Net-(LED8-DOUT)") (class "Default")
      (node (ref "LED8") (pin "2") (pinfunction "DOUT_2") (pintype "passive"))
      (node (ref "LED9") (pin "4") (pinfunction "DIN_4") (pintype "passive"))
    )
    (net (code "24") (name "Net-(LED10-DIN)") (class "Default")
      (node (ref "LED10") (pin "4") (pinfunction "DIN_4") (pintype "passive"))
      (node (ref "LED9") (pin "2") (pinfunction "DOUT_2") (pintype "passive"))
    )
    (net (code "25") (name "Net-(LED10-DOUT)") (class "Default")
      (node (ref "LED10") (pin "2") (pinfunction "DOUT_2") (pintype "passive"))
      (node (ref "LED11") (pin "4") (pinfunction "DIN_4") (pintype "passive"))
    )
    (net (code "26") (name "Net-(LED11-DOUT)") (class "Default")
      (node (ref "LED11") (pin "2") (pinfunction "DOUT_2") (pintype "passive"))
      (node (ref "LED12") (pin "4") (pinfunction "DIN_4") (pintype "passive"))
    )
    (net (code "27") (name "Net-(LED13-DOUT)") (class "Default")
      (node (ref "LED13") (pin "2") (pinfunction "DOUT_2") (pintype "passive"))
      (node (ref "LED14") (pin "4") (pinfunction "DIN_4") (pintype "passive"))
    )
    (net (code "28") (name "Net-(LED14-DOUT)") (class "Default")
      (node (ref "LED14") (pin "2") (pinfunction "DOUT_2") (pintype "passive"))
      (node (ref "LED15") (pin "4") (pinfunction "DIN_4") (pintype "passive"))
    )
    (net (code "29") (name "Net-(LED15-DOUT)") (class "Default")
      (node (ref "LED15") (pin "2") (pinfunction "DOUT_2") (pintype "passive"))
      (node (ref "LED16") (pin "4") (pinfunction "DIN_4") (pintype "passive"))
    )
    (net (code "30") (name "Net-(LED16-DOUT)") (class "Default")
      (node (ref "LED16") (pin "2") (pinfunction "DOUT_2") (pintype "passive"))
      (node (ref "LED17") (pin "4") (pinfunction "DIN_4") (pintype "passive"))
    )
    (net (code "31") (name "Net-(LED17-DOUT)") (class "Default")
      (node (ref "LED17") (pin "2") (pinfunction "DOUT_2") (pintype "passive"))
      (node (ref "LED18") (pin "4") (pinfunction "DIN_4") (pintype "passive"))
    )
    (net (code "32") (name "Net-(LED19-DOUT)") (class "Default")
      (node (ref "LED19") (pin "2") (pinfunction "DOUT_2") (pintype "passive"))
      (node (ref "LED20") (pin "4") (pinfunction "DIN_4") (pintype "passive"))
    )
    (net (code "33") (name "Net-(LED20-DOUT)") (class "Default")
      (node (ref "LED20") (pin "2") (pinfunction "DOUT_2") (pintype "passive"))
      (node (ref "LED21") (pin "4") (pinfunction "DIN_4") (pintype "passive"))
    )
    (net (code "34") (name "Net-(LED21-DOUT)") (class "Default")
      (node (ref "LED21") (pin "2") (pinfunction "DOUT_2") (pintype "passive"))
      (node (ref "LED22") (pin "4") (pinfunction "DIN_4") (pintype "passive"))
    )
    (net (code "35") (name "Net-(LED22-DOUT)") (class "Default")
      (node (ref "LED22") (pin "2") (pinfunction "DOUT_2") (pintype "passive"))
      (node (ref "LED23") (pin "4") (pinfunction "DIN_4") (pintype "passive"))
    )
    (net (code "36") (name "Net-(LED23-DOUT)") (class "Default")
      (node (ref "LED23") (pin "2") (pinfunction "DOUT_2") (pintype "passive"))
      (node (ref "LED24") (pin "4") (pinfunction "DIN_4") (pintype "passive"))
    )
    (net (code "37") (name "Net-(LED25-DOUT)") (class "Default")
      (node (ref "LED25") (pin "2") (pinfunction "DOUT_2") (pintype "passive"))
      (node (ref "LED26") (pin "4") (pinfunction "DIN_4") (pintype "passive"))
    )
    (net (code "38") (name "Net-(LED26-DOUT)") (class "Default")
      (node (ref "LED26") (pin "2") (pinfunction "DOUT_2") (pintype "passive"))
      (node (ref "LED27") (pin "4") (pinfunction "DIN_4") (pintype "passive"))
    )
    (net (code "39") (name "Net-(LED27-DOUT)") (class "Default")
      (node (ref "LED27") (pin "2") (pinfunction "DOUT_2") (pintype "passive"))
      (node (ref "LED28") (pin "4") (pinfunction "DIN_4") (pintype "passive"))
    )
    (net (code "40") (name "Net-(LED28-DOUT)") (class "Default")
      (node (ref "LED28") (pin "2") (pinfunction "DOUT_2") (pintype "passive"))
      (node (ref "LED29") (pin "4") (pinfunction "DIN_4") (pintype "passive"))
    )
    (net (code "41") (name "Net-(LED29-DOUT)") (class "Default")
      (node (ref "LED29") (pin "2") (pinfunction "DOUT_2") (pintype "passive"))
      (node (ref "LED30") (pin "4") (pinfunction "DIN_4") (pintype "passive"))
    )
    (net (code "42") (name "Net-(LED31-DOUT)") (class "Default")
      (node (ref "LED31") (pin "2") (pinfunction "DOUT_2") (pintype "passive"))
      (node (ref "LED32") (pin "4") (pinfunction "DIN_4") (pintype "passive"))
    )
    (net (code "43") (name "Net-(LED32-DOUT)") (class "Default")
      (node (ref "LED32") (pin "2") (pinfunction "DOUT_2") (pintype "passive"))
      (node (ref "LED33") (pin "4") (pinfunction "DIN_4") (pintype "passive"))
    )
    (net (code "44") (name "Net-(LED33-DOUT)") (class "Default")
      (node (ref "LED33") (pin "2") (pinfunction "DOUT_2") (pintype "passive"))
      (node (ref "LED34") (pin "4") (pinfunction "DIN_4") (pintype "passive"))
    )
    (net (code "45") (name "Net-(LED34-DOUT)") (class "Default")
      (node (ref "LED34") (pin "2") (pinfunction "DOUT_2") (pintype "passive"))
      (node (ref "LED35") (pin "4") (pinfunction "DIN_4") (pintype "passive"))
    )
    (net (code "46") (name "Net-(LED35-DOUT)") (class "Default")
      (node (ref "LED35") (pin "2") (pinfunction "DOUT_2") (pintype "passive"))
      (node (ref "LED36") (pin "4") (pinfunction "DIN_4") (pintype "passive"))
    )
    (net (code "47") (name "Net-(U1-EN(CH-PD))") (class "Default")
      (node (ref "R1") (pin "2") (pinfunction "2_2") (pintype "passive"))
      (node (ref "U1") (pin "3") (pinfunction "EN(CH-PD)_3") (pintype "passive"))
    )
    (net (code "48") (name "Net-(U1-IO2)") (class "Default")
      (node (ref "R5") (pin "1") (pinfunction "1_1") (pintype "passive"))
      (node (ref "U1") (pin "11") (pinfunction "IO2_11") (pintype "passive"))
    )
    (net (code "49") (name "Net-(U1-IO15)") (class "Default")
      (node (ref "R4") (pin "1") (pinfunction "1_1") (pintype "passive"))
      (node (ref "U1") (pin "10") (pinfunction "IO15_10") (pintype "passive"))
    )
    (net (code "50") (name "Net-(U1-RXD0)") (class "Default")
      (node (ref "R3") (pin "1") (pinfunction "1_1") (pintype "passive"))
      (node (ref "U1") (pin "15") (pinfunction "RXD0_15") (pintype "passive"))
    )
    (net (code "51") (name "Net-(U2-BP{slash}FB)") (class "Default")
      (node (ref "C33") (pin "1") (pinfunction "1_1") (pintype "passive"))
      (node (ref "U2") (pin "4") (pinfunction "BP/FB_4") (pintype "passive"))
    )
    (net (code "52") (name "VCC") (class "Default")
      (node (ref "C1") (pin "1") (pinfunction "1_1") (pintype "passive"))
      (node (ref "C10") (pin "1") (pinfunction "1_1") (pintype "passive"))
      (node (ref "C11") (pin "1") (pinfunction "1_1") (pintype "passive"))
      (node (ref "C12") (pin "1") (pinfunction "1_1") (pintype "passive"))
      (node (ref "C13") (pin "1") (pinfunction "1_1") (pintype "passive"))
      (node (ref "C14") (pin "1") (pinfunction "1_1") (pintype "passive"))
      (node (ref "C15") (pin "1") (pinfunction "1_1") (pintype "passive"))
      (node (ref "C16") (pin "1") (pinfunction "1_1") (pintype "passive"))
      (node (ref "C18") (pin "1") (pinfunction "1_1") (pintype "passive"))
      (node (ref "C19") (pin "1") (pinfunction "1_1") (pintype "passive"))
      (node (ref "C2") (pin "1") (pinfunction "1_1") (pintype "passive"))
      (node (ref "C20") (pin "1") (pinfunction "1_1") (pintype "passive"))
      (node (ref "C21") (pin "1") (pinfunction "1_1") (pintype "passive"))
      (node (ref "C22") (pin "1") (pinfunction "1_1") (pintype "passive"))
      (node (ref "C23") (pin "1") (pinfunction "1_1") (pintype "passive"))
      (node (ref "C24") (pin "1") (pinfunction "1_1") (pintype "passive"))
      (node (ref "C25") (pin "1") (pinfunction "1_1") (pintype "passive"))
      (node (ref "C26") (pin "1") (pinfunction "1_1") (pintype "passive"))
      (node (ref "C27") (pin "1") (pinfunction "1_1") (pintype "passive"))
      (node (ref "C28") (pin "1") (pinfunction "1_1") (pintype "passive"))
      (node (ref "C29") (pin "1") (pinfunction "1_1") (pintype "passive"))
      (node (ref "C3") (pin "1") (pinfunction "1_1") (pintype "passive"))
      (node (ref "C30") (pin "1") (pinfunction "1_1") (pintype "passive"))
      (node (ref "C31") (pin "1") (pinfunction "1_1") (pintype "passive"))
      (node (ref "C4") (pin "1") (pinfunction "1_1") (pintype "passive"))
      (node (ref "C5") (pin "1") (pinfunction "1_1") (pintype "passive"))
      (node (ref "C6") (pin "1") (pinfunction "1_1") (pintype "passive"))
      (node (ref "C7") (pin "1") (pinfunction "1_1") (pintype "passive"))
      (node (ref "C8") (pin "1") (pinfunction "1_1") (pintype "passive"))
      (node (ref "C9") (pin "1") (pinfunction "1_1") (pintype "passive"))
      (node (ref "JP1") (pin "1") (pinfunction "1_1") (pintype "passive"))
      (node (ref "LED1") (pin "1") (pinfunction "VDD_1") (pintype "passive"))
      (node (ref "LED10") (pin "1") (pinfunction "VDD_1") (pintype "passive"))
      (node (ref "LED11") (pin "1") (pinfunction "VDD_1") (pintype "passive"))
      (node (ref "LED12") (pin "1") (pinfunction "VDD_1") (pintype "passive"))
      (node (ref "LED13") (pin "1") (pinfunction "VDD_1") (pintype "passive"))
      (node (ref "LED14") (pin "1") (pinfunction "VDD_1") (pintype "passive"))
      (node (ref "LED15") (pin "1") (pinfunction "VDD_1") (pintype "passive"))
      (node (ref "LED16") (pin "1") (pinfunction "VDD_1") (pintype "passive"))
      (node (ref "LED17") (pin "1") (pinfunction "VDD_1") (pintype "passive"))
      (node (ref "LED18") (pin "1") (pinfunction "VDD_1") (pintype "passive"))
      (node (ref "LED19") (pin "1") (pinfunction "VDD_1") (pintype "passive"))
      (node (ref "LED2") (pin "1") (pinfunction "VDD_1") (pintype "passive"))
      (node (ref "LED20") (pin "1") (pinfunction "VDD_1") (pintype "passive"))
      (node (ref "LED21") (pin "1") (pinfunction "VDD_1") (pintype "passive"))
      (node (ref "LED22") (pin "1") (pinfunction "VDD_1") (pintype "passive"))
      (node (ref "LED23") (pin "1") (pinfunction "VDD_1") (pintype "passive"))
      (node (ref "LED24") (pin "1") (pinfunction "VDD_1") (pintype "passive"))
      (node (ref "LED25") (pin "1") (pinfunction "VDD_1") (pintype "passive"))
      (node (ref "LED26") (pin "1") (pinfunction "VDD_1") (pintype "passive"))
      (node (ref "LED27") (pin "1") (pinfunction "VDD_1") (pintype "passive"))
      (node (ref "LED28") (pin "1") (pinfunction "VDD_1") (pintype "passive"))
      (node (ref "LED29") (pin "1") (pinfunction "VDD_1") (pintype "passive"))
      (node (ref "LED3") (pin "1") (pinfunction "VDD_1") (pintype "passive"))
      (node (ref "LED30") (pin "1") (pinfunction "VDD_1") (pintype "passive"))
      (node (ref "LED31") (pin "1") (pinfunction "VDD_1") (pintype "passive"))
      (node (ref "LED32") (pin "1") (pinfunction "VDD_1") (pintype "passive"))
      (node (ref "LED33") (pin "1") (pinfunction "VDD_1") (pintype "passive"))
      (node (ref "LED34") (pin "1") (pinfunction "VDD_1") (pintype "passive"))
      (node (ref "LED35") (pin "1") (pinfunction "VDD_1") (pintype "passive"))
      (node (ref "LED36") (pin "1") (pinfunction "VDD_1") (pintype "passive"))
      (node (ref "LED37") (pin "1") (pinfunction "VDD_1") (pintype "passive"))
      (node (ref "LED4") (pin "1") (pinfunction "VDD_1") (pintype "passive"))
      (node (ref "LED5") (pin "1") (pinfunction "VDD_1") (pintype "passive"))
      (node (ref "LED6") (pin "1") (pinfunction "VDD_1") (pintype "passive"))
      (node (ref "LED7") (pin "1") (pinfunction "VDD_1") (pintype "passive"))
      (node (ref "LED8") (pin "1") (pinfunction "VDD_1") (pintype "passive"))
      (node (ref "LED9") (pin "1") (pinfunction "VDD_1") (pintype "passive"))
      (node (ref "U2") (pin "1") (pinfunction "IN_1") (pintype "passive"))
      (node (ref "U2") (pin "3") (pinfunction "EN_3") (pintype "passive"))
      (node (ref "USB1") (pin "A9") (pinfunction "VBUS_A9") (pintype "passive"))
      (node (ref "USB1") (pin "B9") (pinfunction "VBUS_B9") (pintype "passive"))
    )
    (net (code "53") (name "VCC_3.3V") (class "Default")
      (node (ref "C17") (pin "1") (pinfunction "1_1") (pintype "passive"))
      (node (ref "C34") (pin "1") (pinfunction "1_1") (pintype "passive"))
      (node (ref "R1") (pin "1") (pinfunction "1_1") (pintype "passive"))
      (node (ref "R10") (pin "1") (pinfunction "1_1") (pintype "passive"))
      (node (ref "R11") (pin "1") (pinfunction "1_1") (pintype "passive"))
      (node (ref "R2") (pin "1") (pinfunction "1_1") (pintype "passive"))
      (node (ref "R5") (pin "2") (pinfunction "2_2") (pintype "passive"))
      (node (ref "R6") (pin "2") (pinfunction "2_2") (pintype "passive"))
      (node (ref "R7") (pin "1") (pinfunction "1_1") (pintype "passive"))
      (node (ref "R9") (pin "1") (pinfunction "1_1") (pintype "passive"))
      (node (ref "U1") (pin "8") (pinfunction "VCC_8") (pintype "passive"))
      (node (ref "U2") (pin "5") (pinfunction "OUT_5") (pintype "passive"))
    )
    (net (code "54") (name "unconnected-(LED36-DOUT-Pad2)") (class "Default")
      (node (ref "LED36") (pin "2") (pinfunction "DOUT_2") (pintype "passive"))
    )
    (net (code "55") (name "unconnected-(SW1-Pad3)") (class "Default")
      (node (ref "SW1") (pin "3") (pinfunction "3_3") (pintype "passive"))
    )
    (net (code "56") (name "unconnected-(SW1-Pad4)") (class "Default")
      (node (ref "SW1") (pin "4") (pinfunction "4_4") (pintype "passive"))
    )
    (net (code "57") (name "unconnected-(SW2-Pad3)") (class "Default")
      (node (ref "SW2") (pin "3") (pinfunction "3_3") (pintype "passive"))
    )
    (net (code "58") (name "unconnected-(SW2-Pad4)") (class "Default")
      (node (ref "SW2") (pin "4") (pinfunction "4_4") (pintype "passive"))
    )
    (net (code "59") (name "unconnected-(SW3-Pad3)") (class "Default")
      (node (ref "SW3") (pin "3") (pinfunction "3_3") (pintype "passive"))
    )
    (net (code "60") (name "unconnected-(SW3-Pad4)") (class "Default")
      (node (ref "SW3") (pin "4") (pinfunction "4_4") (pintype "passive"))
    )
    (net (code "61") (name "unconnected-(SW4-Pad3)") (class "Default")
      (node (ref "SW4") (pin "3") (pinfunction "3_3") (pintype "passive"))
    )
    (net (code "62") (name "unconnected-(SW4-Pad4)") (class "Default")
      (node (ref "SW4") (pin "4") (pinfunction "4_4") (pintype "passive"))
    )
    (net (code "63") (name "unconnected-(U1-ADC-Pad2)") (class "Default")
      (node (ref "U1") (pin "2") (pinfunction "ADC_2") (pintype "passive+no_connect"))
    )
    (net (code "64") (name "unconnected-(U1-CS0-Pad17)") (class "Default")
      (node (ref "U1") (pin "17") (pinfunction "CS0_17") (pintype "passive"))
    )
    (net (code "65") (name "unconnected-(U1-GPIO16-Pad4)") (class "Default")
      (node (ref "U1") (pin "4") (pinfunction "GPIO16_4") (pintype "passive"))
    )
    (net (code "66") (name "unconnected-(U1-IO4-Pad13)") (class "Default")
      (node (ref "U1") (pin "13") (pinfunction "IO4_13") (pintype "passive"))
    )
    (net (code "67") (name "unconnected-(U1-IO9-Pad19)") (class "Default")
      (node (ref "U1") (pin "19") (pinfunction "IO9_19") (pintype "passive"))
    )
    (net (code "68") (name "unconnected-(U1-MISO-Pad18)") (class "Default")
      (node (ref "U1") (pin "18") (pinfunction "MISO_18") (pintype "passive"))
    )
    (net (code "69") (name "unconnected-(U1-MOSI-Pad21)") (class "Default")
      (node (ref "U1") (pin "21") (pinfunction "MOSI_21") (pintype "passive"))
    )
    (net (code "70") (name "unconnected-(U1-SCLK-Pad22)") (class "Default")
      (node (ref "U1") (pin "22") (pinfunction "SCLK_22") (pintype "passive"))
    )
    (net (code "71") (name "unconnected-(USB1-CC1-PadA5)") (class "Default")
      (node (ref "USB1") (pin "A5") (pinfunction "CC1_A5") (pintype "passive"))
    )
    (net (code "72") (name "unconnected-(USB1-CC2-PadB5)") (class "Default")
      (node (ref "USB1") (pin "B5") (pinfunction "CC2_B5") (pintype "passive"))
    )
  )
)
